# x_carriage.net
KiCad netlist of a schematic drawn in EAGLE
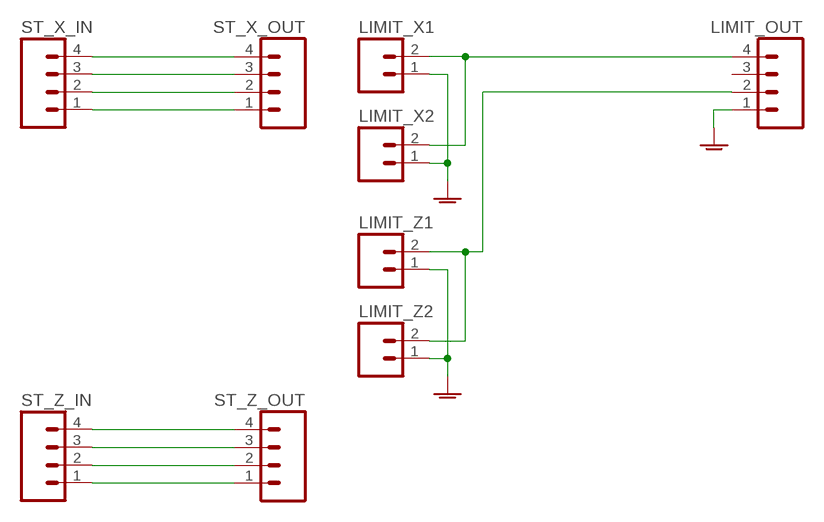
[diagram p0: schematic, sheet 1]

(export (version "E")
  (design (tool "Eeschema 10.0.6"))
  (components
    (comp (ref "LIMIT_OUT")
      (value "M04PTH")
      (footprint "eagle-import:1X04")
      (libsource (lib "eagle-import") (part "M04PTH"))
    )
    (comp (ref "LIMIT_X1")
      (value "M02POLAR")
      (footprint "eagle-import:MOLEX-1X2")
      (libsource (lib "eagle-import") (part "M02POLAR"))
    )
    (comp (ref "LIMIT_X2")
      (value "M02POLAR")
      (footprint "eagle-import:MOLEX-1X2")
      (libsource (lib "eagle-import") (part "M02POLAR"))
    )
    (comp (ref "LIMIT_Z1")
      (value "M02POLAR")
      (footprint "eagle-import:MOLEX-1X2")
      (libsource (lib "eagle-import") (part "M02POLAR"))
    )
    (comp (ref "LIMIT_Z2")
      (value "M02POLAR")
      (footprint "eagle-import:MOLEX-1X2")
      (libsource (lib "eagle-import") (part "M02POLAR"))
    )
    (comp (ref "ST_X_IN")
      (value "M04POLAR")
      (footprint "eagle-import:MOLEX-1X4")
      (libsource (lib "eagle-import") (part "M04POLAR"))
    )
    (comp (ref "ST_X_OUT")
      (value "M04PTH")
      (footprint "eagle-import:1X04")
      (libsource (lib "eagle-import") (part "M04PTH"))
    )
    (comp (ref "ST_Z_IN")
      (value "M04POLAR")
      (footprint "eagle-import:MOLEX-1X4")
      (libsource (lib "eagle-import") (part "M04POLAR"))
    )
    (comp (ref "ST_Z_OUT")
      (value "M04PTH")
      (footprint "eagle-import:1X04")
      (libsource (lib "eagle-import") (part "M04PTH"))
    )
  )
  (nets
    (net (code "1") (name "GNDA") (class "Default")
      (node (ref "LIMIT_OUT") (pin "1") (pinfunction "1_1") (pintype "passive"))
      (node (ref "LIMIT_X1") (pin "1") (pinfunction "1_1") (pintype "passive"))
      (node (ref "LIMIT_X2") (pin "1") (pinfunction "1_1") (pintype "passive"))
      (node (ref "LIMIT_Z1") (pin "1") (pinfunction "1_1") (pintype "passive"))
      (node (ref "LIMIT_Z2") (pin "1") (pinfunction "1_1") (pintype "passive"))
    )
    (net (code "2") (name "Net-(LIMIT_OUT-Pad2)") (class "Default")
      (node (ref "LIMIT_OUT") (pin "2") (pinfunction "2_2") (pintype "passive"))
      (node (ref "LIMIT_Z1") (pin "2") (pinfunction "2_2") (pintype "passive"))
      (node (ref "LIMIT_Z2") (pin "2") (pinfunction "2_2") (pintype "passive"))
    )
    (net (code "3") (name "Net-(LIMIT_OUT-Pad4)") (class "Default")
      (node (ref "LIMIT_OUT") (pin "4") (pinfunction "4_4") (pintype "passive"))
      (node (ref "LIMIT_X1") (pin "2") (pinfunction "2_2") (pintype "passive"))
      (node (ref "LIMIT_X2") (pin "2") (pinfunction "2_2") (pintype "passive"))
    )
    (net (code "4") (name "Net-(ST_X_IN-Pad1)") (class "Default")
      (node (ref "ST_X_IN") (pin "1") (pinfunction "1_1") (pintype "passive"))
      (node (ref "ST_X_OUT") (pin "1") (pinfunction "1_1") (pintype "passive"))
    )
    (net (code "5") (name "Net-(ST_X_IN-Pad2)") (class "Default")
      (node (ref "ST_X_IN") (pin "2") (pinfunction "2_2") (pintype "passive"))
      (node (ref "ST_X_OUT") (pin "2") (pinfunction "2_2") (pintype "passive"))
    )
    (net (code "6") (name "Net-(ST_X_IN-Pad3)") (class "Default")
      (node (ref "ST_X_IN") (pin "3") (pinfunction "3_3") (pintype "passive"))
      (node (ref "ST_X_OUT") (pin "3") (pinfunction "3_3") (pintype "passive"))
    )
    (net (code "7") (name "Net-(ST_X_IN-Pad4)") (class "Default")
      (node (ref "ST_X_IN") (pin "4") (pinfunction "4_4") (pintype "passive"))
      (node (ref "ST_X_OUT") (pin "4") (pinfunction "4_4") (pintype "passive"))
    )
    (net (code "8") (name "Net-(ST_Z_IN-Pad1)") (class "Default")
      (node (ref "ST_Z_IN") (pin "1") (pinfunction "1_1") (pintype "passive"))
      (node (ref "ST_Z_OUT") (pin "1") (pinfunction "1_1") (pintype "passive"))
    )
    (net (code "9") (name "Net-(ST_Z_IN-Pad2)") (class "Default")
      (node (ref "ST_Z_IN") (pin "2") (pinfunction "2_2") (pintype "passive"))
      (node (ref "ST_Z_OUT") (pin "2") (pinfunction "2_2") (pintype "passive"))
    )
    (net (code "10") (name "Net-(ST_Z_IN-Pad3)") (class "Default")
      (node (ref "ST_Z_IN") (pin "3") (pinfunction "3_3") (pintype "passive"))
      (node (ref "ST_Z_OUT") (pin "3") (pinfunction "3_3") (pintype "passive"))
    )
    (net (code "11") (name "Net-(ST_Z_IN-Pad4)") (class "Default")
      (node (ref "ST_Z_IN") (pin "4") (pinfunction "4_4") (pintype "passive"))
      (node (ref "ST_Z_OUT") (pin "4") (pinfunction "4_4") (pintype "passive"))
    )
    (net (code "12") (name "unconnected-(LIMIT_OUT-Pad3)") (class "Default")
      (node (ref "LIMIT_OUT") (pin "3") (pinfunction "3_3") (pintype "passive"))
    )
  )
)
